# 4_HDMI_ETH.net
KiCad netlist of a schematic drawn in Altium Designer
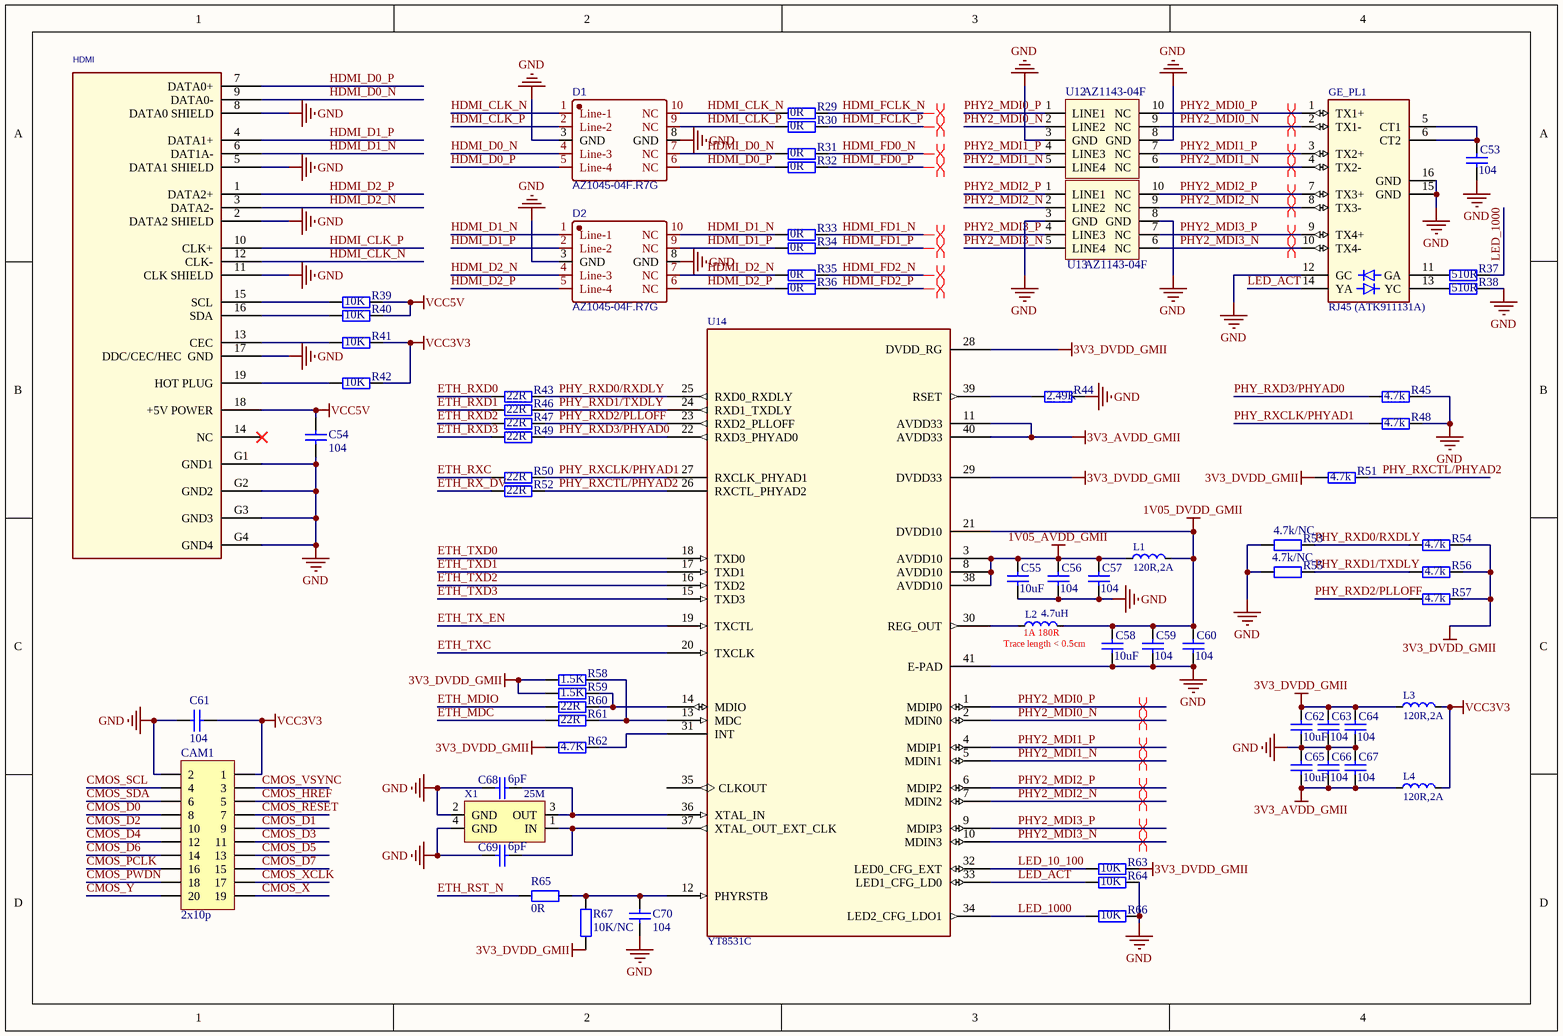
[diagram p0: 4_HDMI+ETH.SchDoc]

(export (version "E")
  (design (tool "Eeschema 10.0.6"))
  (components
    (comp (ref "C53")
      (value "104")
      (footprint "C 0603")
      (libsource (lib "ATK-DFPGL25G&50G_V1.3") (part "C-0603-SMD"))
    )
    (comp (ref "C54")
      (value "104")
      (footprint "C 0603")
      (libsource (lib "ATK-DFPGL25G&50G_V1.3") (part "C-0603-SMD"))
    )
    (comp (ref "C55")
      (value "10uF")
      (footprint "C 0603")
      (libsource (lib "ATK-DFPGL25G&50G_V1.3") (part "C-0603-SMD"))
    )
    (comp (ref "C56")
      (value "104")
      (footprint "C 0603")
      (libsource (lib "ATK-DFPGL25G&50G_V1.3") (part "C-0603-SMD"))
    )
    (comp (ref "C57")
      (value "104")
      (footprint "C 0603")
      (libsource (lib "ATK-DFPGL25G&50G_V1.3") (part "C-0603-SMD"))
    )
    (comp (ref "C58")
      (value "10uF")
      (footprint "C 0603")
      (libsource (lib "ATK-DFPGL25G&50G_V1.3") (part "C-0603-SMD"))
    )
    (comp (ref "C59")
      (value "104")
      (footprint "C 0603")
      (libsource (lib "ATK-DFPGL25G&50G_V1.3") (part "C-0603-SMD"))
    )
    (comp (ref "C60")
      (value "104")
      (footprint "C 0603")
      (libsource (lib "ATK-DFPGL25G&50G_V1.3") (part "C-0603-SMD"))
    )
    (comp (ref "C61")
      (value "104")
      (footprint "C 0603")
      (libsource (lib "ATK-DFPGL25G&50G_V1.3") (part "C-0603-SMD"))
    )
    (comp (ref "C62")
      (value "10uF")
      (footprint "C 0603")
      (libsource (lib "ATK-DFPGL25G&50G_V1.3") (part "C-0603-SMD"))
    )
    (comp (ref "C63")
      (value "104")
      (footprint "C 0603")
      (libsource (lib "ATK-DFPGL25G&50G_V1.3") (part "C-0603-SMD"))
    )
    (comp (ref "C64")
      (value "104")
      (footprint "C 0603")
      (libsource (lib "ATK-DFPGL25G&50G_V1.3") (part "C-0603-SMD"))
    )
    (comp (ref "C65")
      (value "10uF")
      (footprint "C 0603")
      (libsource (lib "ATK-DFPGL25G&50G_V1.3") (part "C-0603-SMD"))
    )
    (comp (ref "C66")
      (value "104")
      (footprint "C 0603")
      (libsource (lib "ATK-DFPGL25G&50G_V1.3") (part "C-0603-SMD"))
    )
    (comp (ref "C67")
      (value "104")
      (footprint "C 0603")
      (libsource (lib "ATK-DFPGL25G&50G_V1.3") (part "C-0603-SMD"))
    )
    (comp (ref "C68")
      (value "6pF")
      (footprint "C 0603")
      (libsource (lib "ATK-DFPGL25G&50G_V1.3") (part "C-0603-SMD"))
    )
    (comp (ref "C69")
      (value "6pF")
      (footprint "C 0603")
      (libsource (lib "ATK-DFPGL25G&50G_V1.3") (part "C-0603-SMD"))
    )
    (comp (ref "C70")
      (value "104")
      (footprint "C 0603")
      (libsource (lib "ATK-DFPGL25G&50G_V1.3") (part "C-0603-SMD"))
    )
    (comp (ref "CAM1")
      (value "2x10p")
      (footprint "HEAD_2X10P")
      (libsource (lib "ATK-DFPGL25G&50G_V1.3") (part "2x10p"))
    )
    (comp (ref "D1")
      (value "AZ1045-04F.R7G")
      (footprint "DFN2510P10E")
      (fields (field (name "BOM_SUPPLIER PART") "C356811") (field (name "CONTRIBUTOR") "LCSC"))
      (libsource (lib "ATK-DFPGL25G&50G_V1.3") (part "AZ1045-04F.R7G"))
    )
    (comp (ref "D2")
      (value "AZ1045-04F.R7G")
      (footprint "DFN2510P10E")
      (fields (field (name "BOM_SUPPLIER PART") "C356811") (field (name "CONTRIBUTOR") "LCSC"))
      (libsource (lib "ATK-DFPGL25G&50G_V1.3") (part "AZ1045-04F.R7G"))
    )
    (comp (ref "GE_PL1")
      (value "RJ45 (ATK911131A)")
      (footprint "HR911131A")
      (description "千兆以太网接口")
      (libsource (lib "PIONEER") (part "HR911131A/C"))
    )
    (comp (ref "HDMI")
      (value "HDMI")
      (footprint "HDMI-A")
      (libsource (lib "ATK-DFPGL25G&50G_V1.3") (part "HDMI_A"))
    )
    (comp (ref "L1")
      (value "120R,2A")
      (footprint "L 0603")
      (description "小功率贴片电感磁珠")
      (libsource (lib "PIONEER") (part "L"))
    )
    (comp (ref "L2")
      (value "4.7uH")
      (footprint "L-2520")
      (description "小功率贴片电感磁珠")
      (libsource (lib "PIONEER") (part "L"))
    )
    (comp (ref "L3")
      (value "120R,2A")
      (footprint "L 0603")
      (description "小功率贴片电感磁珠")
      (libsource (lib "PIONEER") (part "L"))
    )
    (comp (ref "L4")
      (value "120R,2A")
      (footprint "L 0603")
      (description "小功率贴片电感磁珠")
      (libsource (lib "PIONEER") (part "L"))
    )
    (comp (ref "R29")
      (value "0R")
      (footprint "R 0603")
      (description "电阻")
      (fields (field (name "版权归属") "正点原子"))
      (libsource (lib "ATK-DFPGL25G&50G_V1.3") (part "R"))
    )
    (comp (ref "R30")
      (value "0R")
      (footprint "R 0603")
      (description "电阻")
      (fields (field (name "版权归属") "正点原子"))
      (libsource (lib "ATK-DFPGL25G&50G_V1.3") (part "R"))
    )
    (comp (ref "R31")
      (value "0R")
      (footprint "R 0603")
      (description "电阻")
      (fields (field (name "版权归属") "正点原子"))
      (libsource (lib "ATK-DFPGL25G&50G_V1.3") (part "R"))
    )
    (comp (ref "R32")
      (value "0R")
      (footprint "R 0603")
      (description "电阻")
      (fields (field (name "版权归属") "正点原子"))
      (libsource (lib "ATK-DFPGL25G&50G_V1.3") (part "R"))
    )
    (comp (ref "R33")
      (value "0R")
      (footprint "R 0603")
      (description "电阻")
      (fields (field (name "版权归属") "正点原子"))
      (libsource (lib "ATK-DFPGL25G&50G_V1.3") (part "R"))
    )
    (comp (ref "R34")
      (value "0R")
      (footprint "R 0603")
      (description "电阻")
      (fields (field (name "版权归属") "正点原子"))
      (libsource (lib "ATK-DFPGL25G&50G_V1.3") (part "R"))
    )
    (comp (ref "R35")
      (value "0R")
      (footprint "R 0603")
      (description "电阻")
      (fields (field (name "版权归属") "正点原子"))
      (libsource (lib "ATK-DFPGL25G&50G_V1.3") (part "R"))
    )
    (comp (ref "R36")
      (value "0R")
      (footprint "R 0603")
      (description "电阻")
      (fields (field (name "版权归属") "正点原子"))
      (libsource (lib "ATK-DFPGL25G&50G_V1.3") (part "R"))
    )
    (comp (ref "R37")
      (value "510R")
      (footprint "R 0603")
      (description "电阻")
      (fields (field (name "版权归属") "正点原子"))
      (libsource (lib "ATK-DFPGL25G&50G_V1.3") (part "R"))
    )
    (comp (ref "R38")
      (value "510R")
      (footprint "R 0603")
      (description "电阻")
      (fields (field (name "版权归属") "正点原子"))
      (libsource (lib "ATK-DFPGL25G&50G_V1.3") (part "R"))
    )
    (comp (ref "R39")
      (value "10K")
      (footprint "R 0603")
      (description "电阻")
      (fields (field (name "版权归属") "正点原子"))
      (libsource (lib "ATK-DFPGL25G&50G_V1.3") (part "R"))
    )
    (comp (ref "R40")
      (value "10K")
      (footprint "R 0603")
      (description "电阻")
      (fields (field (name "版权归属") "正点原子"))
      (libsource (lib "ATK-DFPGL25G&50G_V1.3") (part "R"))
    )
    (comp (ref "R41")
      (value "10K")
      (footprint "R 0603")
      (description "电阻")
      (fields (field (name "版权归属") "正点原子"))
      (libsource (lib "ATK-DFPGL25G&50G_V1.3") (part "R"))
    )
    (comp (ref "R42")
      (value "10K")
      (footprint "R 0603")
      (description "电阻")
      (fields (field (name "版权归属") "正点原子"))
      (libsource (lib "ATK-DFPGL25G&50G_V1.3") (part "R"))
    )
    (comp (ref "R43")
      (value "22R")
      (footprint "R 0603")
      (description "电阻")
      (fields (field (name "版权归属") "正点原子"))
      (libsource (lib "ATK-DFPGL25G&50G_V1.3") (part "R"))
    )
    (comp (ref "R44")
      (value "2.49K")
      (footprint "R 0603")
      (description "电阻")
      (fields (field (name "版权归属") "正点原子"))
      (libsource (lib "ATK-DFPGL25G&50G_V1.3") (part "R"))
    )
    (comp (ref "R45")
      (value "4.7k")
      (footprint "R 0603")
      (description "电阻")
      (fields (field (name "版权归属") "正点原子"))
      (libsource (lib "ATK-DFPGL25G&50G_V1.3") (part "R"))
    )
    (comp (ref "R46")
      (value "22R")
      (footprint "R 0603")
      (description "电阻")
      (fields (field (name "版权归属") "正点原子"))
      (libsource (lib "ATK-DFPGL25G&50G_V1.3") (part "R"))
    )
    (comp (ref "R47")
      (value "22R")
      (footprint "R 0603")
      (description "电阻")
      (fields (field (name "版权归属") "正点原子"))
      (libsource (lib "ATK-DFPGL25G&50G_V1.3") (part "R"))
    )
    (comp (ref "R48")
      (value "4.7k")
      (footprint "R 0603")
      (description "电阻")
      (fields (field (name "版权归属") "正点原子"))
      (libsource (lib "ATK-DFPGL25G&50G_V1.3") (part "R"))
    )
    (comp (ref "R49")
      (value "22R")
      (footprint "R 0603")
      (description "电阻")
      (fields (field (name "版权归属") "正点原子"))
      (libsource (lib "ATK-DFPGL25G&50G_V1.3") (part "R"))
    )
    (comp (ref "R50")
      (value "22R")
      (footprint "R 0603")
      (description "电阻")
      (fields (field (name "版权归属") "正点原子"))
      (libsource (lib "ATK-DFPGL25G&50G_V1.3") (part "R"))
    )
    (comp (ref "R51")
      (value "4.7k")
      (footprint "R 0603")
      (description "电阻")
      (fields (field (name "版权归属") "正点原子"))
      (libsource (lib "ATK-DFPGL25G&50G_V1.3") (part "R"))
    )
    (comp (ref "R52")
      (value "22R")
      (footprint "R 0603")
      (description "电阻")
      (fields (field (name "版权归属") "正点原子"))
      (libsource (lib "ATK-DFPGL25G&50G_V1.3") (part "R"))
    )
    (comp (ref "R53")
      (value "4.7k/NC")
      (footprint "R 0603")
      (description "电阻")
      (fields (field (name "版权归属") "正点原子"))
      (libsource (lib "ATK-DFPGL25G&50G_V1.3") (part "R"))
    )
    (comp (ref "R54")
      (value "4.7k")
      (footprint "R 0603")
      (description "电阻")
      (fields (field (name "版权归属") "正点原子"))
      (libsource (lib "ATK-DFPGL25G&50G_V1.3") (part "R"))
    )
    (comp (ref "R55")
      (value "4.7k/NC")
      (footprint "R 0603")
      (description "电阻")
      (fields (field (name "版权归属") "正点原子"))
      (libsource (lib "ATK-DFPGL25G&50G_V1.3") (part "R"))
    )
    (comp (ref "R56")
      (value "4.7k")
      (footprint "R 0603")
      (description "电阻")
      (fields (field (name "版权归属") "正点原子"))
      (libsource (lib "ATK-DFPGL25G&50G_V1.3") (part "R"))
    )
    (comp (ref "R57")
      (value "4.7k")
      (footprint "R 0603")
      (description "电阻")
      (fields (field (name "版权归属") "正点原子"))
      (libsource (lib "ATK-DFPGL25G&50G_V1.3") (part "R"))
    )
    (comp (ref "R58")
      (value "1.5K")
      (footprint "R 0603")
      (description "电阻")
      (fields (field (name "版权归属") "正点原子"))
      (libsource (lib "ATK-DFPGL25G&50G_V1.3") (part "R"))
    )
    (comp (ref "R59")
      (value "1.5K")
      (footprint "R 0603")
      (description "电阻")
      (fields (field (name "版权归属") "正点原子"))
      (libsource (lib "ATK-DFPGL25G&50G_V1.3") (part "R"))
    )
    (comp (ref "R60")
      (value "22R")
      (footprint "R 0603")
      (description "电阻")
      (fields (field (name "版权归属") "正点原子"))
      (libsource (lib "ATK-DFPGL25G&50G_V1.3") (part "R"))
    )
    (comp (ref "R61")
      (value "22R")
      (footprint "R 0603")
      (description "电阻")
      (fields (field (name "版权归属") "正点原子"))
      (libsource (lib "ATK-DFPGL25G&50G_V1.3") (part "R"))
    )
    (comp (ref "R62")
      (value "4.7K")
      (footprint "R 0603")
      (description "电阻")
      (fields (field (name "版权归属") "正点原子"))
      (libsource (lib "ATK-DFPGL25G&50G_V1.3") (part "R"))
    )
    (comp (ref "R63")
      (value "10K")
      (footprint "R 0603")
      (description "电阻")
      (fields (field (name "版权归属") "正点原子"))
      (libsource (lib "ATK-DFPGL25G&50G_V1.3") (part "R"))
    )
    (comp (ref "R64")
      (value "10K")
      (footprint "R 0603")
      (description "电阻")
      (fields (field (name "版权归属") "正点原子"))
      (libsource (lib "ATK-DFPGL25G&50G_V1.3") (part "R"))
    )
    (comp (ref "R65")
      (value "0R")
      (footprint "R 0603")
      (description "电阻")
      (fields (field (name "版权归属") "正点原子"))
      (libsource (lib "ATK-DFPGL25G&50G_V1.3") (part "R"))
    )
    (comp (ref "R66")
      (value "10K")
      (footprint "R 0603")
      (description "电阻")
      (fields (field (name "版权归属") "正点原子"))
      (libsource (lib "ATK-DFPGL25G&50G_V1.3") (part "R"))
    )
    (comp (ref "R67")
      (value "10K/NC")
      (footprint "R 0603")
      (description "电阻")
      (fields (field (name "版权归属") "正点原子"))
      (libsource (lib "ATK-DFPGL25G&50G_V1.3") (part "R"))
    )
    (comp (ref "U12")
      (value "AZ1143-04F")
      (footprint "DFN2510P10E")
      (description "ESD保护二极管阵列")
      (libsource (lib "PIONEER") (part "AZ1143-04F"))
    )
    (comp (ref "U13")
      (value "AZ1143-04F")
      (footprint "DFN2510P10E")
      (description "ESD保护二极管阵列")
      (libsource (lib "PIONEER") (part "AZ1143-04F"))
    )
    (comp (ref "U14")
      (value "YT8531C")
      (footprint "QFN40 5X5_N")
      (libsource (lib "PIONEER") (part "RTL8211F-CG"))
    )
    (comp (ref "X1")
      (value "25M")
      (footprint "XTAL-3225")
      (description "4脚无源晶振")
      (libsource (lib "PIONEER") (part "XTAL-4P"))
    )
  )
  (nets
    (net (code "1") (name "/CMOS_D0") (class "Default")
      (node (ref "CAM1") (pin "8") (pinfunction "8_8") (pintype "passive"))
    )
    (net (code "2") (name "/CMOS_D1") (class "Default")
      (node (ref "CAM1") (pin "9") (pinfunction "9_9") (pintype "passive"))
    )
    (net (code "3") (name "/CMOS_D2") (class "Default")
      (node (ref "CAM1") (pin "10") (pinfunction "10_10") (pintype "passive"))
    )
    (net (code "4") (name "/CMOS_D3") (class "Default")
      (node (ref "CAM1") (pin "11") (pinfunction "11_11") (pintype "passive"))
    )
    (net (code "5") (name "/CMOS_D4") (class "Default")
      (node (ref "CAM1") (pin "12") (pinfunction "12_12") (pintype "passive"))
    )
    (net (code "6") (name "/CMOS_D5") (class "Default")
      (node (ref "CAM1") (pin "13") (pinfunction "13_13") (pintype "passive"))
    )
    (net (code "7") (name "/CMOS_D6") (class "Default")
      (node (ref "CAM1") (pin "14") (pinfunction "14_14") (pintype "passive"))
    )
    (net (code "8") (name "/CMOS_D7") (class "Default")
      (node (ref "CAM1") (pin "15") (pinfunction "15_15") (pintype "passive"))
    )
    (net (code "9") (name "/CMOS_HREF") (class "Default")
      (node (ref "CAM1") (pin "5") (pinfunction "5_5") (pintype "passive"))
    )
    (net (code "10") (name "/CMOS_PCLK") (class "Default")
      (node (ref "CAM1") (pin "16") (pinfunction "16_16") (pintype "passive"))
    )
    (net (code "11") (name "/CMOS_PWDN") (class "Default")
      (node (ref "CAM1") (pin "18") (pinfunction "18_18") (pintype "passive"))
    )
    (net (code "12") (name "/CMOS_RESET") (class "Default")
      (node (ref "CAM1") (pin "7") (pinfunction "7_7") (pintype "passive"))
    )
    (net (code "13") (name "/CMOS_SCL") (class "Default")
      (node (ref "CAM1") (pin "4") (pinfunction "4_4") (pintype "passive"))
    )
    (net (code "14") (name "/CMOS_SDA") (class "Default")
      (node (ref "CAM1") (pin "6") (pinfunction "6_6") (pintype "passive"))
    )
    (net (code "15") (name "/CMOS_VSYNC") (class "Default")
      (node (ref "CAM1") (pin "3") (pinfunction "3_3") (pintype "passive"))
    )
    (net (code "16") (name "/CMOS_X") (class "Default")
      (node (ref "CAM1") (pin "19") (pinfunction "19_19") (pintype "passive"))
    )
    (net (code "17") (name "/CMOS_XCLK") (class "Default")
      (node (ref "CAM1") (pin "17") (pinfunction "17_17") (pintype "passive"))
    )
    (net (code "18") (name "/CMOS_Y") (class "Default")
      (node (ref "CAM1") (pin "20") (pinfunction "20_20") (pintype "passive"))
    )
    (net (code "19") (name "/ETH_MDC") (class "Default")
      (node (ref "R61") (pin "1") (pinfunction "1_1") (pintype "passive"))
    )
    (net (code "20") (name "/ETH_MDIO") (class "Default")
      (node (ref "R60") (pin "1") (pinfunction "1_1") (pintype "passive"))
    )
    (net (code "21") (name "/ETH_RST_N") (class "Default")
      (node (ref "R65") (pin "2") (pinfunction "2_2") (pintype "passive"))
    )
    (net (code "22") (name "/ETH_RXC") (class "Default")
      (node (ref "R50") (pin "1") (pinfunction "1_1") (pintype "passive"))
    )
    (net (code "23") (name "/ETH_RXD0") (class "Default")
      (node (ref "R43") (pin "1") (pinfunction "1_1") (pintype "passive"))
    )
    (net (code "24") (name "/ETH_RXD1") (class "Default")
      (node (ref "R46") (pin "1") (pinfunction "1_1") (pintype "passive"))
    )
    (net (code "25") (name "/ETH_RXD2") (class "Default")
      (node (ref "R47") (pin "1") (pinfunction "1_1") (pintype "passive"))
    )
    (net (code "26") (name "/ETH_RXD3") (class "Default")
      (node (ref "R49") (pin "1") (pinfunction "1_1") (pintype "passive"))
    )
    (net (code "27") (name "/ETH_RX_DV") (class "Default")
      (node (ref "R52") (pin "1") (pinfunction "1_1") (pintype "passive"))
    )
    (net (code "28") (name "/ETH_TXC") (class "Default")
      (node (ref "U14") (pin "20") (pinfunction "TXCLK_20") (pintype "input"))
    )
    (net (code "29") (name "/ETH_TXD0") (class "Default")
      (node (ref "U14") (pin "18") (pinfunction "TXD0_18") (pintype "input"))
    )
    (net (code "30") (name "/ETH_TXD1") (class "Default")
      (node (ref "U14") (pin "17") (pinfunction "TXD1_17") (pintype "input"))
    )
    (net (code "31") (name "/ETH_TXD2") (class "Default")
      (node (ref "U14") (pin "16") (pinfunction "TXD2_16") (pintype "input"))
    )
    (net (code "32") (name "/ETH_TXD3") (class "Default")
      (node (ref "U14") (pin "15") (pinfunction "TXD3_15") (pintype "input"))
    )
    (net (code "33") (name "/ETH_TX_EN") (class "Default")
      (node (ref "U14") (pin "19") (pinfunction "TXCTL_19") (pintype "input"))
    )
    (net (code "34") (name "/HDMI_CLK_N") (class "Default")
      (node (ref "D1") (pin "1") (pinfunction "Line-1_1") (pintype "passive"))
      (node (ref "D1") (pin "10") (pinfunction "NC_10") (pintype "passive"))
      (node (ref "HDMI") (pin "12") (pinfunction "CLK-_12") (pintype "passive"))
      (node (ref "R29") (pin "1") (pinfunction "1_1") (pintype "passive"))
    )
    (net (code "35") (name "/HDMI_CLK_P") (class "Default")
      (node (ref "D1") (pin "2") (pinfunction "Line-2_2") (pintype "passive"))
      (node (ref "D1") (pin "9") (pinfunction "NC_9") (pintype "passive"))
      (node (ref "HDMI") (pin "10") (pinfunction "CLK+_10") (pintype "passive"))
      (node (ref "R30") (pin "1") (pinfunction "1_1") (pintype "passive"))
    )
    (net (code "36") (name "/HDMI_D0_N") (class "Default")
      (node (ref "D1") (pin "4") (pinfunction "Line-3_4") (pintype "passive"))
      (node (ref "D1") (pin "7") (pinfunction "NC_7") (pintype "passive"))
      (node (ref "HDMI") (pin "9") (pinfunction "DATA0-_9") (pintype "passive"))
      (node (ref "R31") (pin "1") (pinfunction "1_1") (pintype "passive"))
    )
    (net (code "37") (name "/HDMI_D0_P") (class "Default")
      (node (ref "D1") (pin "5") (pinfunction "Line-4_5") (pintype "passive"))
      (node (ref "D1") (pin "6") (pinfunction "NC_6") (pintype "passive"))
      (node (ref "HDMI") (pin "7") (pinfunction "DATA0+_7") (pintype "passive"))
      (node (ref "R32") (pin "1") (pinfunction "1_1") (pintype "passive"))
    )
    (net (code "38") (name "/HDMI_D1_N") (class "Default")
      (node (ref "D2") (pin "1") (pinfunction "Line-1_1") (pintype "passive"))
      (node (ref "D2") (pin "10") (pinfunction "NC_10") (pintype "passive"))
      (node (ref "HDMI") (pin "6") (pinfunction "DAT1A-_6") (pintype "passive"))
      (node (ref "R33") (pin "1") (pinfunction "1_1") (pintype "passive"))
    )
    (net (code "39") (name "/HDMI_D1_P") (class "Default")
      (node (ref "D2") (pin "2") (pinfunction "Line-2_2") (pintype "passive"))
      (node (ref "D2") (pin "9") (pinfunction "NC_9") (pintype "passive"))
      (node (ref "HDMI") (pin "4") (pinfunction "DATA1+_4") (pintype "passive"))
      (node (ref "R34") (pin "1") (pinfunction "1_1") (pintype "passive"))
    )
    (net (code "40") (name "/HDMI_D2_N") (class "Default")
      (node (ref "D2") (pin "4") (pinfunction "Line-3_4") (pintype "passive"))
      (node (ref "D2") (pin "7") (pinfunction "NC_7") (pintype "passive"))
      (node (ref "HDMI") (pin "3") (pinfunction "DATA2-_3") (pintype "passive"))
      (node (ref "R35") (pin "1") (pinfunction "1_1") (pintype "passive"))
    )
    (net (code "41") (name "/HDMI_D2_P") (class "Default")
      (node (ref "D2") (pin "5") (pinfunction "Line-4_5") (pintype "passive"))
      (node (ref "D2") (pin "6") (pinfunction "NC_6") (pintype "passive"))
      (node (ref "HDMI") (pin "1") (pinfunction "DATA2+_1") (pintype "passive"))
      (node (ref "R36") (pin "1") (pinfunction "1_1") (pintype "passive"))
    )
    (net (code "42") (name "/HDMI_FCLK_N") (class "Default")
      (node (ref "R29") (pin "2") (pinfunction "2_2") (pintype "passive"))
    )
    (net (code "43") (name "/HDMI_FCLK_P") (class "Default")
      (node (ref "R30") (pin "2") (pinfunction "2_2") (pintype "passive"))
    )
    (net (code "44") (name "/HDMI_FD0_N") (class "Default")
      (node (ref "R31") (pin "2") (pinfunction "2_2") (pintype "passive"))
    )
    (net (code "45") (name "/HDMI_FD0_P") (class "Default")
      (node (ref "R32") (pin "2") (pinfunction "2_2") (pintype "passive"))
    )
    (net (code "46") (name "/HDMI_FD1_N") (class "Default")
      (node (ref "R33") (pin "2") (pinfunction "2_2") (pintype "passive"))
    )
    (net (code "47") (name "/HDMI_FD1_P") (class "Default")
      (node (ref "R34") (pin "2") (pinfunction "2_2") (pintype "passive"))
    )
    (net (code "48") (name "/HDMI_FD2_N") (class "Default")
      (node (ref "R35") (pin "2") (pinfunction "2_2") (pintype "passive"))
    )
    (net (code "49") (name "/HDMI_FD2_P") (class "Default")
      (node (ref "R36") (pin "2") (pinfunction "2_2") (pintype "passive"))
    )
    (net (code "50") (name "/LED_10_100") (class "Default")
      (node (ref "R63") (pin "1") (pinfunction "1_1") (pintype "passive"))
      (node (ref "U14") (pin "32") (pinfunction "LED0_CFG_EXT_32") (pintype "bidirectional"))
    )
    (net (code "51") (name "/LED_1000") (class "Default")
      (node (ref "R37") (pin "2") (pinfunction "2_2") (pintype "passive"))
      (node (ref "R66") (pin "1") (pinfunction "1_1") (pintype "passive"))
      (node (ref "U14") (pin "34") (pinfunction "LED2_CFG_LDO1_34") (pintype "output"))
    )
    (net (code "52") (name "/LED_ACT") (class "Default")
      (node (ref "GE_PL1") (pin "14") (pinfunction "YA_14") (pintype "passive"))
      (node (ref "R64") (pin "1") (pinfunction "1_1") (pintype "passive"))
      (node (ref "U14") (pin "33") (pinfunction "LED1_CFG_LD0_33") (pintype "bidirectional"))
    )
    (net (code "53") (name "/PHY2_MDI0_N") (class "Default")
      (node (ref "GE_PL1") (pin "2") (pinfunction "TX1-_2") (pintype "bidirectional"))
      (node (ref "U12") (pin "2") (pinfunction "LINE2_2") (pintype "passive"))
      (node (ref "U12") (pin "9") (pinfunction "NC_9") (pintype "passive"))
      (node (ref "U14") (pin "2") (pinfunction "MDIN0_2") (pintype "bidirectional"))
    )
    (net (code "54") (name "/PHY2_MDI0_P") (class "Default")
      (node (ref "GE_PL1") (pin "1") (pinfunction "TX1+_1") (pintype "bidirectional"))
      (node (ref "U12") (pin "1") (pinfunction "LINE1_1") (pintype "passive"))
      (node (ref "U12") (pin "10") (pinfunction "NC_10") (pintype "passive"))
      (node (ref "U14") (pin "1") (pinfunction "MDIP0_1") (pintype "bidirectional"))
    )
    (net (code "55") (name "/PHY2_MDI1_N") (class "Default")
      (node (ref "GE_PL1") (pin "4") (pinfunction "TX2-_4") (pintype "bidirectional"))
      (node (ref "U12") (pin "5") (pinfunction "LINE4_5") (pintype "passive"))
      (node (ref "U12") (pin "6") (pinfunction "NC_6") (pintype "passive"))
      (node (ref "U14") (pin "5") (pinfunction "MDIN1_5") (pintype "bidirectional"))
    )
    (net (code "56") (name "/PHY2_MDI1_P") (class "Default")
      (node (ref "GE_PL1") (pin "3") (pinfunction "TX2+_3") (pintype "bidirectional"))
      (node (ref "U12") (pin "4") (pinfunction "LINE3_4") (pintype "passive"))
      (node (ref "U12") (pin "7") (pinfunction "NC_7") (pintype "passive"))
      (node (ref "U14") (pin "4") (pinfunction "MDIP1_4") (pintype "bidirectional"))
    )
    (net (code "57") (name "/PHY2_MDI2_N") (class "Default")
      (node (ref "GE_PL1") (pin "8") (pinfunction "TX3-_8") (pintype "bidirectional"))
      (node (ref "U13") (pin "2") (pinfunction "LINE2_2") (pintype "passive"))
      (node (ref "U13") (pin "9") (pinfunction "NC_9") (pintype "passive"))
      (node (ref "U14") (pin "7") (pinfunction "MDIN2_7") (pintype "bidirectional"))
    )
    (net (code "58") (name "/PHY2_MDI2_P") (class "Default")
      (node (ref "GE_PL1") (pin "7") (pinfunction "TX3+_7") (pintype "bidirectional"))
      (node (ref "U13") (pin "1") (pinfunction "LINE1_1") (pintype "passive"))
      (node (ref "U13") (pin "10") (pinfunction "NC_10") (pintype "passive"))
      (node (ref "U14") (pin "6") (pinfunction "MDIP2_6") (pintype "bidirectional"))
    )
    (net (code "59") (name "/PHY2_MDI3_N") (class "Default")
      (node (ref "GE_PL1") (pin "10") (pinfunction "TX4-_10") (pintype "bidirectional"))
      (node (ref "U13") (pin "5") (pinfunction "LINE4_5") (pintype "passive"))
      (node (ref "U13") (pin "6") (pinfunction "NC_6") (pintype "passive"))
      (node (ref "U14") (pin "10") (pinfunction "MDIN3_10") (pintype "bidirectional"))
    )
    (net (code "60") (name "/PHY2_MDI3_P") (class "Default")
      (node (ref "GE_PL1") (pin "9") (pinfunction "TX4+_9") (pintype "bidirectional"))
      (node (ref "U13") (pin "4") (pinfunction "LINE3_4") (pintype "passive"))
      (node (ref "U13") (pin "7") (pinfunction "NC_7") (pintype "passive"))
      (node (ref "U14") (pin "9") (pinfunction "MDIP3_9") (pintype "bidirectional"))
    )
    (net (code "61") (name "/PHY_RXCLK{slash}PHYAD1") (class "Default")
      (node (ref "R48") (pin "1") (pinfunction "1_1") (pintype "passive"))
      (node (ref "R50") (pin "2") (pinfunction "2_2") (pintype "passive"))
      (node (ref "U14") (pin "27") (pinfunction "RXCLK_PHYAD1_27") (pintype "passive"))
    )
    (net (code "62") (name "/PHY_RXCTL{slash}PHYAD2") (class "Default")
      (node (ref "R51") (pin "2") (pinfunction "2_2") (pintype "passive"))
      (node (ref "R52") (pin "2") (pinfunction "2_2") (pintype "passive"))
      (node (ref "U14") (pin "26") (pinfunction "RXCTL_PHYAD2_26") (pintype "passive"))
    )
    (net (code "63") (name "/PHY_RXD0{slash}RXDLY") (class "Default")
      (node (ref "R43") (pin "2") (pinfunction "2_2") (pintype "passive"))
      (node (ref "R53") (pin "2") (pinfunction "2_2") (pintype "passive"))
      (node (ref "R54") (pin "1") (pinfunction "1_1") (pintype "passive"))
      (node (ref "U14") (pin "25") (pinfunction "RXD0_RXDLY_25") (pintype "output"))
    )
    (net (code "64") (name "/PHY_RXD1{slash}TXDLY") (class "Default")
      (node (ref "R46") (pin "2") (pinfunction "2_2") (pintype "passive"))
      (node (ref "R55") (pin "2") (pinfunction "2_2") (pintype "passive"))
      (node (ref "R56") (pin "1") (pinfunction "1_1") (pintype "passive"))
      (node (ref "U14") (pin "24") (pinfunction "RXD1_TXDLY_24") (pintype "output"))
    )
    (net (code "65") (name "/PHY_RXD2{slash}PLLOFF") (class "Default")
      (node (ref "R47") (pin "2") (pinfunction "2_2") (pintype "passive"))
      (node (ref "R57") (pin "1") (pinfunction "1_1") (pintype "passive"))
      (node (ref "U14") (pin "23") (pinfunction "RXD2_PLLOFF_23") (pintype "output"))
    )
    (net (code "66") (name "/PHY_RXD3{slash}PHYAD0") (class "Default")
      (node (ref "R45") (pin "1") (pinfunction "1_1") (pintype "passive"))
      (node (ref "R49") (pin "2") (pinfunction "2_2") (pintype "passive"))
      (node (ref "U14") (pin "22") (pinfunction "RXD3_PHYAD0_22") (pintype "output"))
    )
    (net (code "67") (name "1V05_AVDD_GMII") (class "Default")
      (node (ref "C55") (pin "1") (pinfunction "1_1") (pintype "passive"))
      (node (ref "C56") (pin "1") (pinfunction "1_1") (pintype "passive"))
      (node (ref "C57") (pin "1") (pinfunction "1_1") (pintype "passive"))
      (node (ref "L1") (pin "1") (pinfunction "1_1") (pintype "passive"))
      (node (ref "U14") (pin "3") (pinfunction "AVDD10_3") (pintype "power_in"))
      (node (ref "U14") (pin "38") (pinfunction "AVDD10_38") (pintype "power_in"))
      (node (ref "U14") (pin "8") (pinfunction "AVDD10_8") (pintype "power_in"))
    )
    (net (code "68") (name "1V05_DVDD_GMII") (class "Default")
      (node (ref "C58") (pin "1") (pinfunction "1_1") (pintype "passive"))
      (node (ref "C59") (pin "1") (pinfunction "1_1") (pintype "passive"))
      (node (ref "C60") (pin "1") (pinfunction "1_1") (pintype "passive"))
      (node (ref "L1") (pin "2") (pinfunction "2_2") (pintype "passive"))
      (node (ref "L2") (pin "2") (pinfunction "2_2") (pintype "passive"))
      (node (ref "U14") (pin "21") (pinfunction "DVDD10_21") (pintype "power_in"))
    )
    (net (code "69") (name "3V3_AVDD_GMII") (class "Default")
      (node (ref "C65") (pin "2") (pinfunction "2_2") (pintype "passive"))
      (node (ref "C66") (pin "2") (pinfunction "2_2") (pintype "passive"))
      (node (ref "C67") (pin "2") (pinfunction "2_2") (pintype "passive"))
      (node (ref "L4") (pin "1") (pinfunction "1_1") (pintype "passive"))
      (node (ref "U14") (pin "11") (pinfunction "AVDD33_11") (pintype "power_in"))
      (node (ref "U14") (pin "40") (pinfunction "AVDD33_40") (pintype "power_in"))
    )
    (net (code "70") (name "3V3_DVDD_GMII") (class "Default")
      (node (ref "C62") (pin "1") (pinfunction "1_1") (pintype "passive"))
      (node (ref "C63") (pin "1") (pinfunction "1_1") (pintype "passive"))
      (node (ref "C64") (pin "1") (pinfunction "1_1") (pintype "passive"))
      (node (ref "L3") (pin "1") (pinfunction "1_1") (pintype "passive"))
      (node (ref "R51") (pin "1") (pinfunction "1_1") (pintype "passive"))
      (node (ref "R54") (pin "2") (pinfunction "2_2") (pintype "passive"))
      (node (ref "R56") (pin "2") (pinfunction "2_2") (pintype "passive"))
      (node (ref "R57") (pin "2") (pinfunction "2_2") (pintype "passive"))
      (node (ref "R58") (pin "1") (pinfunction "1_1") (pintype "passive"))
      (node (ref "R59") (pin "1") (pinfunction "1_1") (pintype "passive"))
      (node (ref "R62") (pin "1") (pinfunction "1_1") (pintype "passive"))
      (node (ref "R63") (pin "2") (pinfunction "2_2") (pintype "passive"))
      (node (ref "R67") (pin "1") (pinfunction "1_1") (pintype "passive"))
      (node (ref "U14") (pin "28") (pinfunction "DVDD_RG_28") (pintype "power_in"))
      (node (ref "U14") (pin "29") (pinfunction "DVDD33_29") (pintype "power_in"))
    )
    (net (code "71") (name "GND") (class "Default")
      (node (ref "C53") (pin "2") (pinfunction "2_2") (pintype "passive"))
      (node (ref "C54") (pin "2") (pinfunction "2_2") (pintype "passive"))
      (node (ref "C55") (pin "2") (pinfunction "2_2") (pintype "passive"))
      (node (ref "C56") (pin "2") (pinfunction "2_2") (pintype "passive"))
      (node (ref "C57") (pin "2") (pinfunction "2_2") (pintype "passive"))
      (node (ref "C58") (pin "2") (pinfunction "2_2") (pintype "passive"))
      (node (ref "C59") (pin "2") (pinfunction "2_2") (pintype "passive"))
      (node (ref "C60") (pin "2") (pinfunction "2_2") (pintype "passive"))
      (node (ref "C61") (pin "2") (pinfunction "2_2") (pintype "passive"))
      (node (ref "C62") (pin "2") (pinfunction "2_2") (pintype "passive"))
      (node (ref "C63") (pin "2") (pinfunction "2_2") (pintype "passive"))
      (node (ref "C64") (pin "2") (pinfunction "2_2") (pintype "passive"))
      (node (ref "C65") (pin "1") (pinfunction "1_1") (pintype "passive"))
      (node (ref "C66") (pin "1") (pinfunction "1_1") (pintype "passive"))
      (node (ref "C67") (pin "1") (pinfunction "1_1") (pintype "passive"))
      (node (ref "C68") (pin "2") (pinfunction "2_2") (pintype "passive"))
      (node (ref "C69") (pin "2") (pinfunction "2_2") (pintype "passive"))
      (node (ref "C70") (pin "2") (pinfunction "2_2") (pintype "passive"))
      (node (ref "CAM1") (pin "2") (pinfunction "2_2") (pintype "passive"))
      (node (ref "D1") (pin "3") (pinfunction "GND_3") (pintype "passive"))
      (node (ref "D1") (pin "8") (pinfunction "GND_8") (pintype "passive"))
      (node (ref "D2") (pin "3") (pinfunction "GND_3") (pintype "passive"))
      (node (ref "D2") (pin "8") (pinfunction "GND_8") (pintype "passive"))
      (node (ref "GE_PL1") (pin "12") (pinfunction "GC_12") (pintype "passive"))
      (node (ref "GE_PL1") (pin "15") (pinfunction "GND_15") (pintype "power_in"))
      (node (ref "GE_PL1") (pin "16") (pinfunction "GND_16") (pintype "power_in"))
      (node (ref "HDMI") (pin "11") (pinfunction "CLK_SHIELD_11") (pintype "passive"))
      (node (ref "HDMI") (pin "17") (pinfunction "DDC/CEC/HEC__GND_17") (pintype "passive"))
      (node (ref "HDMI") (pin "2") (pinfunction "DATA2_SHIELD_2") (pintype "passive"))
      (node (ref "HDMI") (pin "5") (pinfunction "DATA1_SHIELD_5") (pintype "passive"))
      (node (ref "HDMI") (pin "8") (pinfunction "DATA0_SHIELD_8") (pintype "passive"))
      (node (ref "HDMI") (pin "G1") (pinfunction "GND1_G1") (pintype "passive"))
      (node (ref "HDMI") (pin "G2") (pinfunction "GND2_G2") (pintype "passive"))
      (node (ref "HDMI") (pin "G3") (pinfunction "GND3_G3") (pintype "passive"))
      (node (ref "HDMI") (pin "G4") (pinfunction "GND4_G4") (pintype "passive"))
      (node (ref "R38") (pin "2") (pinfunction "2_2") (pintype "passive"))
      (node (ref "R44") (pin "2") (pinfunction "2_2") (pintype "passive"))
      (node (ref "R45") (pin "2") (pinfunction "2_2") (pintype "passive"))
      (node (ref "R48") (pin "2") (pinfunction "2_2") (pintype "passive"))
      (node (ref "R53") (pin "1") (pinfunction "1_1") (pintype "passive"))
      (node (ref "R55") (pin "1") (pinfunction "1_1") (pintype "passive"))
      (node (ref "R64") (pin "2") (pinfunction "2_2") (pintype "passive"))
      (node (ref "R66") (pin "2") (pinfunction "2_2") (pintype "passive"))
      (node (ref "U12") (pin "3") (pinfunction "GND_3") (pintype "passive"))
      (node (ref "U12") (pin "8") (pinfunction "GND_8") (pintype "passive"))
      (node (ref "U13") (pin "3") (pinfunction "GND_3") (pintype "passive"))
      (node (ref "U13") (pin "8") (pinfunction "GND_8") (pintype "passive"))
      (node (ref "U14") (pin "41") (pinfunction "E-PAD_41") (pintype "power_in"))
      (node (ref "X1") (pin "2") (pinfunction "GND_2") (pintype "passive"))
      (node (ref "X1") (pin "4") (pinfunction "GND_4") (pintype "passive"))
    )
    (net (code "72") (name "Net-(GE_PL1-CT1)") (class "Default")
      (node (ref "C53") (pin "1") (pinfunction "1_1") (pintype "passive"))
      (node (ref "GE_PL1") (pin "5") (pinfunction "CT1_5") (pintype "passive"))
      (node (ref "GE_PL1") (pin "6") (pinfunction "CT2_6") (pintype "passive"))
    )
    (net (code "73") (name "Net-(GE_PL1-GA)") (class "Default")
      (node (ref "GE_PL1") (pin "11") (pinfunction "GA_11") (pintype "passive"))
      (node (ref "R37") (pin "1") (pinfunction "1_1") (pintype "passive"))
    )
    (net (code "74") (name "Net-(GE_PL1-YC)") (class "Default")
      (node (ref "GE_PL1") (pin "13") (pinfunction "YC_13") (pintype "passive"))
      (node (ref "R38") (pin "1") (pinfunction "1_1") (pintype "passive"))
    )
    (net (code "75") (name "Net-(HDMI-CEC)") (class "Default")
      (node (ref "HDMI") (pin "13") (pinfunction "CEC_13") (pintype "passive"))
      (node (ref "R41") (pin "1") (pinfunction "1_1") (pintype "passive"))
    )
    (net (code "76") (name "Net-(HDMI-HOT_PLUG)") (class "Default")
      (node (ref "HDMI") (pin "19") (pinfunction "HOT_PLUG_19") (pintype "passive"))
      (node (ref "R42") (pin "1") (pinfunction "1_1") (pintype "passive"))
    )
    (net (code "77") (name "Net-(HDMI-SCL)") (class "Default")
      (node (ref "HDMI") (pin "15") (pinfunction "SCL_15") (pintype "passive"))
      (node (ref "R39") (pin "1") (pinfunction "1_1") (pintype "passive"))
    )
    (net (code "78") (name "Net-(HDMI-SDA)") (class "Default")
      (node (ref "HDMI") (pin "16") (pinfunction "SDA_16") (pintype "passive"))
      (node (ref "R40") (pin "1") (pinfunction "1_1") (pintype "passive"))
    )
    (net (code "79") (name "Net-(U14-INT)") (class "Default")
      (node (ref "R62") (pin "2") (pinfunction "2_2") (pintype "passive"))
      (node (ref "U14") (pin "31") (pinfunction "INT_31") (pintype "passive"))
    )
    (net (code "80") (name "Net-(U14-MDC)") (class "Default")
      (node (ref "R58") (pin "2") (pinfunction "2_2") (pintype "passive"))
      (node (ref "R61") (pin "2") (pinfunction "2_2") (pintype "passive"))
      (node (ref "U14") (pin "13") (pinfunction "MDC_13") (pintype "input"))
    )
    (net (code "81") (name "Net-(U14-MDIO)") (class "Default")
      (node (ref "R59") (pin "2") (pinfunction "2_2") (pintype "passive"))
      (node (ref "R60") (pin "2") (pinfunction "2_2") (pintype "passive"))
      (node (ref "U14") (pin "14") (pinfunction "MDIO_14") (pintype "bidirectional"))
    )
    (net (code "82") (name "Net-(U14-PHYRSTB)") (class "Default")
      (node (ref "C70") (pin "1") (pinfunction "1_1") (pintype "passive"))
      (node (ref "R65") (pin "1") (pinfunction "1_1") (pintype "passive"))
      (node (ref "R67") (pin "2") (pinfunction "2_2") (pintype "passive"))
      (node (ref "U14") (pin "12") (pinfunction "PHYRSTB_12") (pintype "input"))
    )
    (net (code "83") (name "Net-(U14-REG_OUT)") (class "Default")
      (node (ref "L2") (pin "1") (pinfunction "1_1") (pintype "passive"))
      (node (ref "U14") (pin "30") (pinfunction "REG_OUT_30") (pintype "output"))
    )
    (net (code "84") (name "Net-(U14-RSET)") (class "Default")
      (node (ref "R44") (pin "1") (pinfunction "1_1") (pintype "passive"))
      (node (ref "U14") (pin "39") (pinfunction "RSET_39") (pintype "output"))
    )
    (net (code "85") (name "Net-(U14-XTAL_IN)") (class "Default")
      (node (ref "C68") (pin "1") (pinfunction "1_1") (pintype "passive"))
      (node (ref "U14") (pin "36") (pinfunction "XTAL_IN_36") (pintype "input"))
      (node (ref "X1") (pin "3") (pinfunction "OUT_3") (pintype "passive"))
    )
    (net (code "86") (name "Net-(U14-XTAL_OUT_EXT_CLK)") (class "Default")
      (node (ref "C69") (pin "1") (pinfunction "1_1") (pintype "passive"))
      (node (ref "U14") (pin "37") (pinfunction "XTAL_OUT_EXT_CLK_37") (pintype "output"))
      (node (ref "X1") (pin "1") (pinfunction "IN_1") (pintype "passive"))
    )
    (net (code "87") (name "VCC3V3") (class "Default")
      (node (ref "C61") (pin "1") (pinfunction "1_1") (pintype "passive"))
      (node (ref "CAM1") (pin "1") (pinfunction "1_1") (pintype "passive"))
      (node (ref "L3") (pin "2") (pinfunction "2_2") (pintype "passive"))
      (node (ref "L4") (pin "2") (pinfunction "2_2") (pintype "passive"))
      (node (ref "R41") (pin "2") (pinfunction "2_2") (pintype "passive"))
      (node (ref "R42") (pin "2") (pinfunction "2_2") (pintype "passive"))
    )
    (net (code "88") (name "VCC5V") (class "Default")
      (node (ref "C54") (pin "1") (pinfunction "1_1") (pintype "passive"))
      (node (ref "HDMI") (pin "18") (pinfunction "+5V_POWER_18") (pintype "passive"))
      (node (ref "R39") (pin "2") (pinfunction "2_2") (pintype "passive"))
      (node (ref "R40") (pin "2") (pinfunction "2_2") (pintype "passive"))
    )
    (net (code "89") (name "unconnected-(HDMI-NC-Pad14)") (class "Default")
      (node (ref "HDMI") (pin "14") (pinfunction "NC_14") (pintype "passive+no_connect"))
    )
    (net (code "90") (name "unconnected-(U14-CLKOUT-Pad35)") (class "Default")
      (node (ref "U14") (pin "35") (pinfunction "CLKOUT_35") (pintype "output"))
    )
  )
)
